# Top_Level.net
KiCad netlist of a schematic drawn in Altium Designer
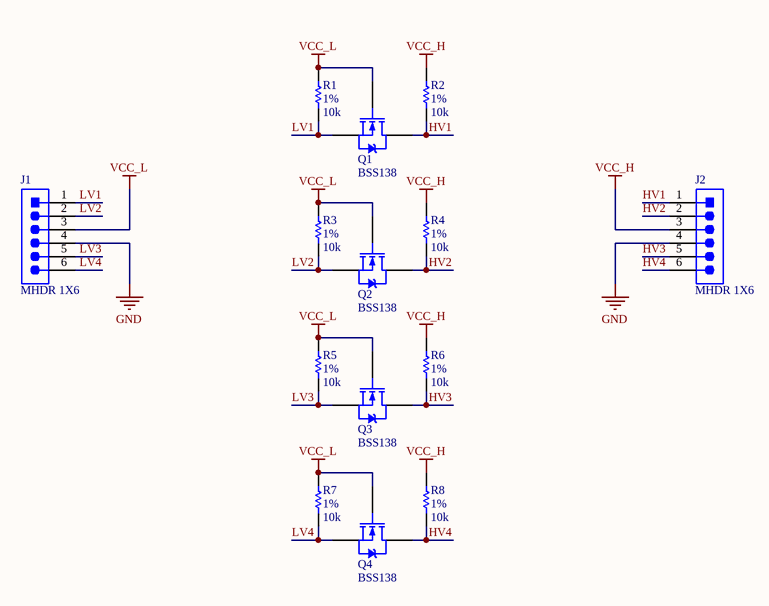
[diagram p0: Top Level.SchDoc]

(export (version "E")
  (design (tool "Eeschema 10.0.6"))
  (components
    (comp (ref "J1")
      (value "MHDR 1X6")
      (footprint "MHDR 1X6")
      (description "Header, 6-Pin, 0.1in Pitch, Male")
      (fields (field (name "JLCPCB PART #") "C178289"))
      (libsource (lib "University of Pennsylvania (ESE Labs)") (part "Header 1X6"))
    )
    (comp (ref "J2")
      (value "MHDR 1X6")
      (footprint "MHDR 1X6")
      (description "Header, 6-Pin, 0.1in Pitch, Male")
      (fields (field (name "JLCPCB PART #") "C178289"))
      (libsource (lib "") (part "Header 1X6_1"))
    )
    (comp (ref "Q1")
      (value "BSS138")
      (footprint "SOT-23-3_ONSEMI")
      (fields (field (name "JLCPCB PART #") "C52895"))
      (libsource (lib "University of Pennsylvania (ESE Labs)") (part "NMOS_1G2S3D"))
    )
    (comp (ref "Q2")
      (value "BSS138")
      (footprint "SOT-23-3_ONSEMI")
      (fields (field (name "JLCPCB PART #") "C52895"))
      (libsource (lib "University of Pennsylvania (ESE Labs)") (part "NMOS_1G2S3D"))
    )
    (comp (ref "Q3")
      (value "BSS138")
      (footprint "SOT-23-3_ONSEMI")
      (fields (field (name "JLCPCB PART #") "C52895"))
      (libsource (lib "University of Pennsylvania (ESE Labs)") (part "NMOS_1G2S3D"))
    )
    (comp (ref "Q4")
      (value "BSS138")
      (footprint "SOT-23-3_ONSEMI")
      (fields (field (name "JLCPCB PART #") "C52895"))
      (libsource (lib "University of Pennsylvania (ESE Labs)") (part "NMOS_1G2S3D"))
    )
    (comp (ref "R1")
      (value "10k")
      (footprint "0603_RES")
      (description "Resistor Surface Mount, 10K Ohms, 0603 Footprint, 1% Tolerance 0.1W")
      (fields
        (field (name "TOLERANCE") "1%")
        (field (name "MANUFACTURER") "Various")
        (field (name "JLCPCB PART #") "C25804")
      )
      (libsource (lib "University of Pennsylvania (ESE Labs)") (part "res"))
    )
    (comp (ref "R2")
      (value "10k")
      (footprint "0603_RES")
      (description "Resistor Surface Mount, 10K Ohms, 0603 Footprint, 1% Tolerance 0.1W")
      (fields
        (field (name "TOLERANCE") "1%")
        (field (name "MANUFACTURER") "Various")
        (field (name "JLCPCB PART #") "C25804")
      )
      (libsource (lib "University of Pennsylvania (ESE Labs)") (part "res"))
    )
    (comp (ref "R3")
      (value "10k")
      (footprint "0603_RES")
      (description "Resistor Surface Mount, 10K Ohms, 0603 Footprint, 1% Tolerance 0.1W")
      (fields
        (field (name "TOLERANCE") "1%")
        (field (name "MANUFACTURER") "Various")
        (field (name "JLCPCB PART #") "C25804")
      )
      (libsource (lib "University of Pennsylvania (ESE Labs)") (part "res"))
    )
    (comp (ref "R4")
      (value "10k")
      (footprint "0603_RES")
      (description "Resistor Surface Mount, 10K Ohms, 0603 Footprint, 1% Tolerance 0.1W")
      (fields
        (field (name "TOLERANCE") "1%")
        (field (name "MANUFACTURER") "Various")
        (field (name "JLCPCB PART #") "C25804")
      )
      (libsource (lib "University of Pennsylvania (ESE Labs)") (part "res"))
    )
    (comp (ref "R5")
      (value "10k")
      (footprint "0603_RES")
      (description "Resistor Surface Mount, 10K Ohms, 0603 Footprint, 1% Tolerance 0.1W")
      (fields
        (field (name "TOLERANCE") "1%")
        (field (name "MANUFACTURER") "Various")
        (field (name "JLCPCB PART #") "C25804")
      )
      (libsource (lib "University of Pennsylvania (ESE Labs)") (part "res"))
    )
    (comp (ref "R6")
      (value "10k")
      (footprint "0603_RES")
      (description "Resistor Surface Mount, 10K Ohms, 0603 Footprint, 1% Tolerance 0.1W")
      (fields
        (field (name "TOLERANCE") "1%")
        (field (name "MANUFACTURER") "Various")
        (field (name "JLCPCB PART #") "C25804")
      )
      (libsource (lib "University of Pennsylvania (ESE Labs)") (part "res"))
    )
    (comp (ref "R7")
      (value "10k")
      (footprint "0603_RES")
      (description "Resistor Surface Mount, 10K Ohms, 0603 Footprint, 1% Tolerance 0.1W")
      (fields
        (field (name "TOLERANCE") "1%")
        (field (name "MANUFACTURER") "Various")
        (field (name "JLCPCB PART #") "C25804")
      )
      (libsource (lib "University of Pennsylvania (ESE Labs)") (part "res"))
    )
    (comp (ref "R8")
      (value "10k")
      (footprint "0603_RES")
      (description "Resistor Surface Mount, 10K Ohms, 0603 Footprint, 1% Tolerance 0.1W")
      (fields
        (field (name "TOLERANCE") "1%")
        (field (name "MANUFACTURER") "Various")
        (field (name "JLCPCB PART #") "C25804")
      )
      (libsource (lib "University of Pennsylvania (ESE Labs)") (part "res"))
    )
  )
  (nets
    (net (code "1") (name "/HV1") (class "Default")
      (node (ref "J2") (pin "1") (pinfunction "1_1") (pintype "passive"))
      (node (ref "Q1") (pin "3") (pinfunction "D_3") (pintype "passive"))
      (node (ref "R2") (pin "1") (pinfunction "1_1") (pintype "passive"))
    )
    (net (code "2") (name "/HV2") (class "Default")
      (node (ref "J2") (pin "2") (pinfunction "2_2") (pintype "passive"))
      (node (ref "Q2") (pin "3") (pinfunction "D_3") (pintype "passive"))
      (node (ref "R4") (pin "1") (pinfunction "1_1") (pintype "passive"))
    )
    (net (code "3") (name "/HV3") (class "Default")
      (node (ref "J2") (pin "5") (pinfunction "5_5") (pintype "passive"))
      (node (ref "Q3") (pin "3") (pinfunction "D_3") (pintype "passive"))
      (node (ref "R6") (pin "1") (pinfunction "1_1") (pintype "passive"))
    )
    (net (code "4") (name "/HV4") (class "Default")
      (node (ref "J2") (pin "6") (pinfunction "6_6") (pintype "passive"))
      (node (ref "Q4") (pin "3") (pinfunction "D_3") (pintype "passive"))
      (node (ref "R8") (pin "1") (pinfunction "1_1") (pintype "passive"))
    )
    (net (code "5") (name "/LV1") (class "Default")
      (node (ref "J1") (pin "1") (pinfunction "1_1") (pintype "passive"))
      (node (ref "Q1") (pin "2") (pinfunction "S_2") (pintype "passive"))
      (node (ref "R1") (pin "1") (pinfunction "1_1") (pintype "passive"))
    )
    (net (code "6") (name "/LV2") (class "Default")
      (node (ref "J1") (pin "2") (pinfunction "2_2") (pintype "passive"))
      (node (ref "Q2") (pin "2") (pinfunction "S_2") (pintype "passive"))
      (node (ref "R3") (pin "1") (pinfunction "1_1") (pintype "passive"))
    )
    (net (code "7") (name "/LV3") (class "Default")
      (node (ref "J1") (pin "5") (pinfunction "5_5") (pintype "passive"))
      (node (ref "Q3") (pin "2") (pinfunction "S_2") (pintype "passive"))
      (node (ref "R5") (pin "1") (pinfunction "1_1") (pintype "passive"))
    )
    (net (code "8") (name "/LV4") (class "Default")
      (node (ref "J1") (pin "6") (pinfunction "6_6") (pintype "passive"))
      (node (ref "Q4") (pin "2") (pinfunction "S_2") (pintype "passive"))
      (node (ref "R7") (pin "1") (pinfunction "1_1") (pintype "passive"))
    )
    (net (code "9") (name "GND") (class "Default")
      (node (ref "J1") (pin "4") (pinfunction "4_4") (pintype "passive"))
      (node (ref "J2") (pin "4") (pinfunction "4_4") (pintype "passive"))
    )
    (net (code "10") (name "VCC_H") (class "Default")
      (node (ref "J2") (pin "3") (pinfunction "3_3") (pintype "passive"))
      (node (ref "R2") (pin "2") (pinfunction "2_2") (pintype "passive"))
      (node (ref "R4") (pin "2") (pinfunction "2_2") (pintype "passive"))
      (node (ref "R6") (pin "2") (pinfunction "2_2") (pintype "passive"))
      (node (ref "R8") (pin "2") (pinfunction "2_2") (pintype "passive"))
    )
    (net (code "11") (name "VCC_L") (class "Default")
      (node (ref "J1") (pin "3") (pinfunction "3_3") (pintype "passive"))
      (node (ref "Q1") (pin "1") (pinfunction "G_1") (pintype "passive"))
      (node (ref "Q2") (pin "1") (pinfunction "G_1") (pintype "passive"))
      (node (ref "Q3") (pin "1") (pinfunction "G_1") (pintype "passive"))
      (node (ref "Q4") (pin "1") (pinfunction "G_1") (pintype "passive"))
      (node (ref "R1") (pin "2") (pinfunction "2_2") (pintype "passive"))
      (node (ref "R3") (pin "2") (pinfunction "2_2") (pintype "passive"))
      (node (ref "R5") (pin "2") (pinfunction "2_2") (pintype "passive"))
      (node (ref "R7") (pin "2") (pinfunction "2_2") (pintype "passive"))
    )
  )
)
